# ut_bbr18_mb_ethernet.net
KiCad netlist of a schematic drawn in Altium Designer
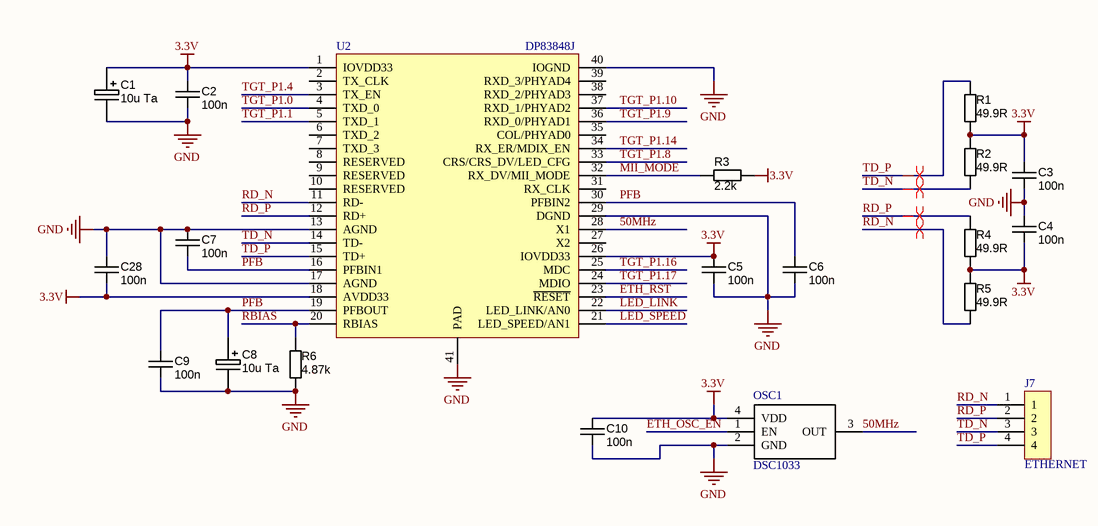
[diagram p0: ut_bbr18_mb_ethernet.SchDoc]

(export (version "E")
  (design (tool "Eeschema 10.0.6"))
  (components
    (comp (ref "C1")
      (value "10u Ta")
      (footprint "CAPMP3528X210N")
      (description "Capacitor SMD Tantalum 47uF 20% 6.3V 1210")
      (fields (field (name "TOLERANCE") "±20%"))
      (libsource (lib "PBL - Capacitors") (part "CAPT_47u_1210_6V3"))
    )
    (comp (ref "C2")
      (value "100n")
      (footprint "CAPC1608X90N")
      (description "Capacitor SMD Cer 18pF 2% 100V NP0 0603")
      (fields (field (name "TOLERANCE") "±2%"))
      (libsource (lib "PBL - Capacitors") (part "CAPC_18p_0603_100V"))
    )
    (comp (ref "C3")
      (value "100n")
      (footprint "CAPC1608X90N")
      (description "Capacitor SMD Cer 18pF 2% 100V NP0 0603")
      (fields (field (name "TOLERANCE") "±2%"))
      (libsource (lib "PBL - Capacitors") (part "CAPC_18p_0603_100V"))
    )
    (comp (ref "C4")
      (value "100n")
      (footprint "CAPC1608X90N")
      (description "Capacitor SMD Cer 18pF 2% 100V NP0 0603")
      (fields (field (name "TOLERANCE") "±2%"))
      (libsource (lib "PBL - Capacitors") (part "CAPC_18p_0603_100V"))
    )
    (comp (ref "C5")
      (value "100n")
      (footprint "CAPC1608X90N")
      (description "Capacitor SMD Cer 18pF 2% 100V NP0 0603")
      (fields (field (name "TOLERANCE") "±2%"))
      (libsource (lib "PBL - Capacitors") (part "CAPC_18p_0603_100V"))
    )
    (comp (ref "C6")
      (value "100n")
      (footprint "CAPC1608X90N")
      (description "Capacitor SMD Cer 18pF 2% 100V NP0 0603")
      (fields (field (name "TOLERANCE") "±2%"))
      (libsource (lib "PBL - Capacitors") (part "CAPC_18p_0603_100V"))
    )
    (comp (ref "C7")
      (value "100n")
      (footprint "CAPC1608X90N")
      (description "Capacitor SMD Cer 18pF 2% 100V NP0 0603")
      (fields (field (name "TOLERANCE") "±2%"))
      (libsource (lib "PBL - Capacitors") (part "CAPC_18p_0603_100V"))
    )
    (comp (ref "C8")
      (value "10u Ta")
      (footprint "CAPMP3528X210N")
      (description "Capacitor SMD Tantalum 47uF 20% 6.3V 1210")
      (fields (field (name "TOLERANCE") "±20%"))
      (libsource (lib "PBL - Capacitors") (part "CAPT_47u_1210_6V3"))
    )
    (comp (ref "C9")
      (value "100n")
      (footprint "CAPC1608X90N")
      (description "Capacitor SMD Cer 18pF 2% 100V NP0 0603")
      (fields (field (name "TOLERANCE") "±2%"))
      (libsource (lib "PBL - Capacitors") (part "CAPC_18p_0603_100V"))
    )
    (comp (ref "C10")
      (value "100n")
      (footprint "CAPC1608X90N")
      (description "Capacitor SMD Cer 18pF 2% 100V NP0 0603")
      (fields (field (name "TOLERANCE") "±2%"))
      (libsource (lib "PBL - Capacitors") (part "CAPC_18p_0603_100V"))
    )
    (comp (ref "C28")
      (value "100n")
      (footprint "CAPC1608X90N")
      (description "Capacitor SMD Cer 18pF 2% 100V NP0 0603")
      (fields (field (name "TOLERANCE") "±2%"))
      (libsource (lib "PBL - Capacitors") (part "CAPC_18p_0603_100V"))
    )
    (comp (ref "J7")
      (value "ETHERNET")
      (footprint "MICRO-MATCH-FOB-04")
      (libsource (lib "connectors_micromatch") (part "HEADER-4"))
    )
    (comp (ref "OSC1")
      (value "DSC1033")
      (footprint "DSC1033-3.2x2.5")
      (libsource (lib "misc") (part "DSC1033"))
    )
    (comp (ref "R1")
      (value "49.9R")
      (footprint "RESC1608X55N")
      (description "Resistor SMD chip 10k Ohm 0.1W 5% 0603")
      (fields (field (name "TOLERANCE") "±5%"))
      (libsource (lib "PBL - Resistors") (part "RES_10K_0603_5%"))
    )
    (comp (ref "R2")
      (value "49.9R")
      (footprint "RESC1608X55N")
      (description "Resistor SMD chip 10k Ohm 0.1W 5% 0603")
      (fields (field (name "TOLERANCE") "±5%"))
      (libsource (lib "PBL - Resistors") (part "RES_10K_0603_5%"))
    )
    (comp (ref "R3")
      (value "2.2k")
      (footprint "RESC1608X55N")
      (description "Resistor SMD chip 10k Ohm 0.1W 5% 0603")
      (fields (field (name "TOLERANCE") "±5%"))
      (libsource (lib "") (part "RES_10K_0603_5%_1"))
    )
    (comp (ref "R4")
      (value "49.9R")
      (footprint "RESC1608X55N")
      (description "Resistor SMD chip 10k Ohm 0.1W 5% 0603")
      (fields (field (name "TOLERANCE") "±5%"))
      (libsource (lib "PBL - Resistors") (part "RES_10K_0603_5%"))
    )
    (comp (ref "R5")
      (value "49.9R")
      (footprint "RESC1608X55N")
      (description "Resistor SMD chip 10k Ohm 0.1W 5% 0603")
      (fields (field (name "TOLERANCE") "±5%"))
      (libsource (lib "PBL - Resistors") (part "RES_10K_0603_5%"))
    )
    (comp (ref "R6")
      (value "4.87k")
      (footprint "RESC1608X55N")
      (description "Resistor SMD chip 10k Ohm 0.1W 5% 0603")
      (fields (field (name "TOLERANCE") "±5%"))
      (libsource (lib "PBL - Resistors") (part "RES_10K_0603_5%"))
    )
    (comp (ref "U2")
      (value "DP83848J")
      (footprint "WQFN40")
      (libsource (lib "texas_instruments") (part "DP83848J"))
    )
  )
  (nets
    (net (code "1") (name "/50MHz") (class "Default")
      (node (ref "OSC1") (pin "3") (pinfunction "OUT_3") (pintype "passive"))
      (node (ref "U2") (pin "28") (pinfunction "X1_28") (pintype "passive"))
    )
    (net (code "2") (name "/ETH_OSC_EN") (class "Default")
      (node (ref "OSC1") (pin "1") (pinfunction "EN_1") (pintype "passive"))
    )
    (net (code "3") (name "/ETH_RST") (class "Default")
      (node (ref "U2") (pin "23") (pinfunction "~{RESET}_23") (pintype "passive"))
    )
    (net (code "4") (name "/LED_LINK") (class "Default")
      (node (ref "U2") (pin "22") (pinfunction "LED_LINK/AN0_22") (pintype "passive"))
    )
    (net (code "5") (name "/LED_SPEED") (class "Default")
      (node (ref "U2") (pin "21") (pinfunction "LED_SPEED/AN1_21") (pintype "passive"))
    )
    (net (code "6") (name "/MII_MODE") (class "Default")
      (node (ref "R3") (pin "2") (pinfunction "2_2") (pintype "passive"))
      (node (ref "U2") (pin "32") (pinfunction "RX_DV/MII_MODE_32") (pintype "passive"))
    )
    (net (code "7") (name "/PFB") (class "Default")
      (node (ref "C6") (pin "2") (pintype "passive"))
      (node (ref "C7") (pin "2") (pintype "passive"))
      (node (ref "C8") (pin "1") (pintype "passive"))
      (node (ref "C9") (pin "2") (pintype "passive"))
      (node (ref "U2") (pin "16") (pinfunction "PFBIN1_16") (pintype "passive"))
      (node (ref "U2") (pin "19") (pinfunction "PFBOUT_19") (pintype "passive"))
      (node (ref "U2") (pin "30") (pinfunction "PFBIN2_30") (pintype "passive"))
    )
    (net (code "8") (name "/RBIAS") (class "Default")
      (node (ref "R6") (pin "1") (pinfunction "1_1") (pintype "passive"))
      (node (ref "U2") (pin "20") (pinfunction "RBIAS_20") (pintype "passive"))
    )
    (net (code "9") (name "/RD_N") (class "Default")
      (node (ref "J7") (pin "1") (pinfunction "1_1") (pintype "passive"))
      (node (ref "R5") (pin "2") (pinfunction "2_2") (pintype "passive"))
      (node (ref "U2") (pin "11") (pinfunction "RD-_11") (pintype "passive"))
    )
    (net (code "10") (name "/RD_P") (class "Default")
      (node (ref "J7") (pin "2") (pinfunction "2_2") (pintype "passive"))
      (node (ref "R4") (pin "1") (pinfunction "1_1") (pintype "passive"))
      (node (ref "U2") (pin "12") (pinfunction "RD+_12") (pintype "passive"))
    )
    (net (code "11") (name "/TD_N") (class "Default")
      (node (ref "J7") (pin "3") (pinfunction "3_3") (pintype "passive"))
      (node (ref "R2") (pin "2") (pinfunction "2_2") (pintype "passive"))
      (node (ref "U2") (pin "14") (pinfunction "TD-_14") (pintype "passive"))
    )
    (net (code "12") (name "/TD_P") (class "Default")
      (node (ref "J7") (pin "4") (pinfunction "4_4") (pintype "passive"))
      (node (ref "R1") (pin "1") (pinfunction "1_1") (pintype "passive"))
      (node (ref "U2") (pin "15") (pinfunction "TD+_15") (pintype "passive"))
    )
    (net (code "13") (name "/TGT_P1.0") (class "Default")
      (node (ref "U2") (pin "4") (pinfunction "TXD_0_4") (pintype "passive"))
    )
    (net (code "14") (name "/TGT_P1.1") (class "Default")
      (node (ref "U2") (pin "5") (pinfunction "TXD_1_5") (pintype "passive"))
    )
    (net (code "15") (name "/TGT_P1.4") (class "Default")
      (node (ref "U2") (pin "3") (pinfunction "TX_EN_3") (pintype "passive"))
    )
    (net (code "16") (name "/TGT_P1.8") (class "Default")
      (node (ref "U2") (pin "33") (pinfunction "CRS/CRS_DV/LED_CFG_33") (pintype "passive"))
    )
    (net (code "17") (name "/TGT_P1.9") (class "Default")
      (node (ref "U2") (pin "36") (pinfunction "RXD_0/PHYAD1_36") (pintype "passive"))
    )
    (net (code "18") (name "/TGT_P1.10") (class "Default")
      (node (ref "U2") (pin "37") (pinfunction "RXD_1/PHYAD2_37") (pintype "passive"))
    )
    (net (code "19") (name "/TGT_P1.14") (class "Default")
      (node (ref "U2") (pin "34") (pinfunction "RX_ER/MDIX_EN_34") (pintype "passive"))
    )
    (net (code "20") (name "/TGT_P1.16") (class "Default")
      (node (ref "U2") (pin "25") (pinfunction "MDC_25") (pintype "passive"))
    )
    (net (code "21") (name "/TGT_P1.17") (class "Default")
      (node (ref "U2") (pin "24") (pinfunction "MDIO_24") (pintype "passive"))
    )
    (net (code "22") (name "3.3V") (class "Default")
      (node (ref "C1") (pin "1") (pintype "passive"))
      (node (ref "C10") (pin "2") (pintype "passive"))
      (node (ref "C2") (pin "2") (pintype "passive"))
      (node (ref "C28") (pin "2") (pintype "passive"))
      (node (ref "C3") (pin "2") (pintype "passive"))
      (node (ref "C4") (pin "1") (pintype "passive"))
      (node (ref "C5") (pin "2") (pintype "passive"))
      (node (ref "OSC1") (pin "4") (pinfunction "VDD_4") (pintype "passive"))
      (node (ref "R1") (pin "2") (pinfunction "2_2") (pintype "passive"))
      (node (ref "R2") (pin "1") (pinfunction "1_1") (pintype "passive"))
      (node (ref "R3") (pin "1") (pinfunction "1_1") (pintype "passive"))
      (node (ref "R4") (pin "2") (pinfunction "2_2") (pintype "passive"))
      (node (ref "R5") (pin "1") (pinfunction "1_1") (pintype "passive"))
      (node (ref "U2") (pin "1") (pinfunction "IOVDD33_1") (pintype "passive"))
      (node (ref "U2") (pin "18") (pinfunction "AVDD33_18") (pintype "passive"))
      (node (ref "U2") (pin "26") (pinfunction "IOVDD33_26") (pintype "passive"))
    )
    (net (code "23") (name "GND") (class "Default")
      (node (ref "C1") (pin "2") (pintype "passive"))
      (node (ref "C10") (pin "1") (pintype "passive"))
      (node (ref "C2") (pin "1") (pintype "passive"))
      (node (ref "C28") (pin "1") (pintype "passive"))
      (node (ref "C3") (pin "1") (pintype "passive"))
      (node (ref "C4") (pin "2") (pintype "passive"))
      (node (ref "C5") (pin "1") (pintype "passive"))
      (node (ref "C6") (pin "1") (pintype "passive"))
      (node (ref "C7") (pin "1") (pintype "passive"))
      (node (ref "C8") (pin "2") (pintype "passive"))
      (node (ref "C9") (pin "1") (pintype "passive"))
      (node (ref "OSC1") (pin "2") (pinfunction "GND_2") (pintype "passive"))
      (node (ref "R6") (pin "2") (pinfunction "2_2") (pintype "passive"))
      (node (ref "U2") (pin "13") (pinfunction "AGND_13") (pintype "passive"))
      (node (ref "U2") (pin "17") (pinfunction "AGND_17") (pintype "passive"))
      (node (ref "U2") (pin "29") (pinfunction "DGND_29") (pintype "passive"))
      (node (ref "U2") (pin "40") (pinfunction "IOGND_40") (pintype "passive"))
      (node (ref "U2") (pin "41") (pinfunction "PAD_41") (pintype "passive"))
    )
    (net (code "24") (name "unconnected-(U2-COL{slash}PHYAD0-Pad35)") (class "Default")
      (node (ref "U2") (pin "35") (pinfunction "COL/PHYAD0_35") (pintype "passive"))
    )
    (net (code "25") (name "unconnected-(U2-RESERVED-Pad8)") (class "Default")
      (node (ref "U2") (pin "8") (pinfunction "RESERVED_8") (pintype "passive"))
    )
    (net (code "26") (name "unconnected-(U2-RESERVED-Pad9)") (class "Default")
      (node (ref "U2") (pin "9") (pinfunction "RESERVED_9") (pintype "passive"))
    )
    (net (code "27") (name "unconnected-(U2-RESERVED-Pad10)") (class "Default")
      (node (ref "U2") (pin "10") (pinfunction "RESERVED_10") (pintype "passive"))
    )
    (net (code "28") (name "unconnected-(U2-RXD_2{slash}PHYAD3-Pad38)") (class "Default")
      (node (ref "U2") (pin "38") (pinfunction "RXD_2/PHYAD3_38") (pintype "passive"))
    )
    (net (code "29") (name "unconnected-(U2-RXD_3{slash}PHYAD4-Pad39)") (class "Default")
      (node (ref "U2") (pin "39") (pinfunction "RXD_3/PHYAD4_39") (pintype "passive"))
    )
    (net (code "30") (name "unconnected-(U2-RX_CLK-Pad31)") (class "Default")
      (node (ref "U2") (pin "31") (pinfunction "RX_CLK_31") (pintype "passive"))
    )
    (net (code "31") (name "unconnected-(U2-TXD_2-Pad6)") (class "Default")
      (node (ref "U2") (pin "6") (pinfunction "TXD_2_6") (pintype "passive"))
    )
    (net (code "32") (name "unconnected-(U2-TXD_3-Pad7)") (class "Default")
      (node (ref "U2") (pin "7") (pinfunction "TXD_3_7") (pintype "passive"))
    )
    (net (code "33") (name "unconnected-(U2-TX_CLK-Pad2)") (class "Default")
      (node (ref "U2") (pin "2") (pinfunction "TX_CLK_2") (pintype "passive"))
    )
    (net (code "34") (name "unconnected-(U2-X2-Pad27)") (class "Default")
      (node (ref "U2") (pin "27") (pinfunction "X2_27") (pintype "passive"))
    )
  )
)
